# MySens-easyESP32-V02b-001.net
KiCad netlist of a schematic drawn in EAGLE
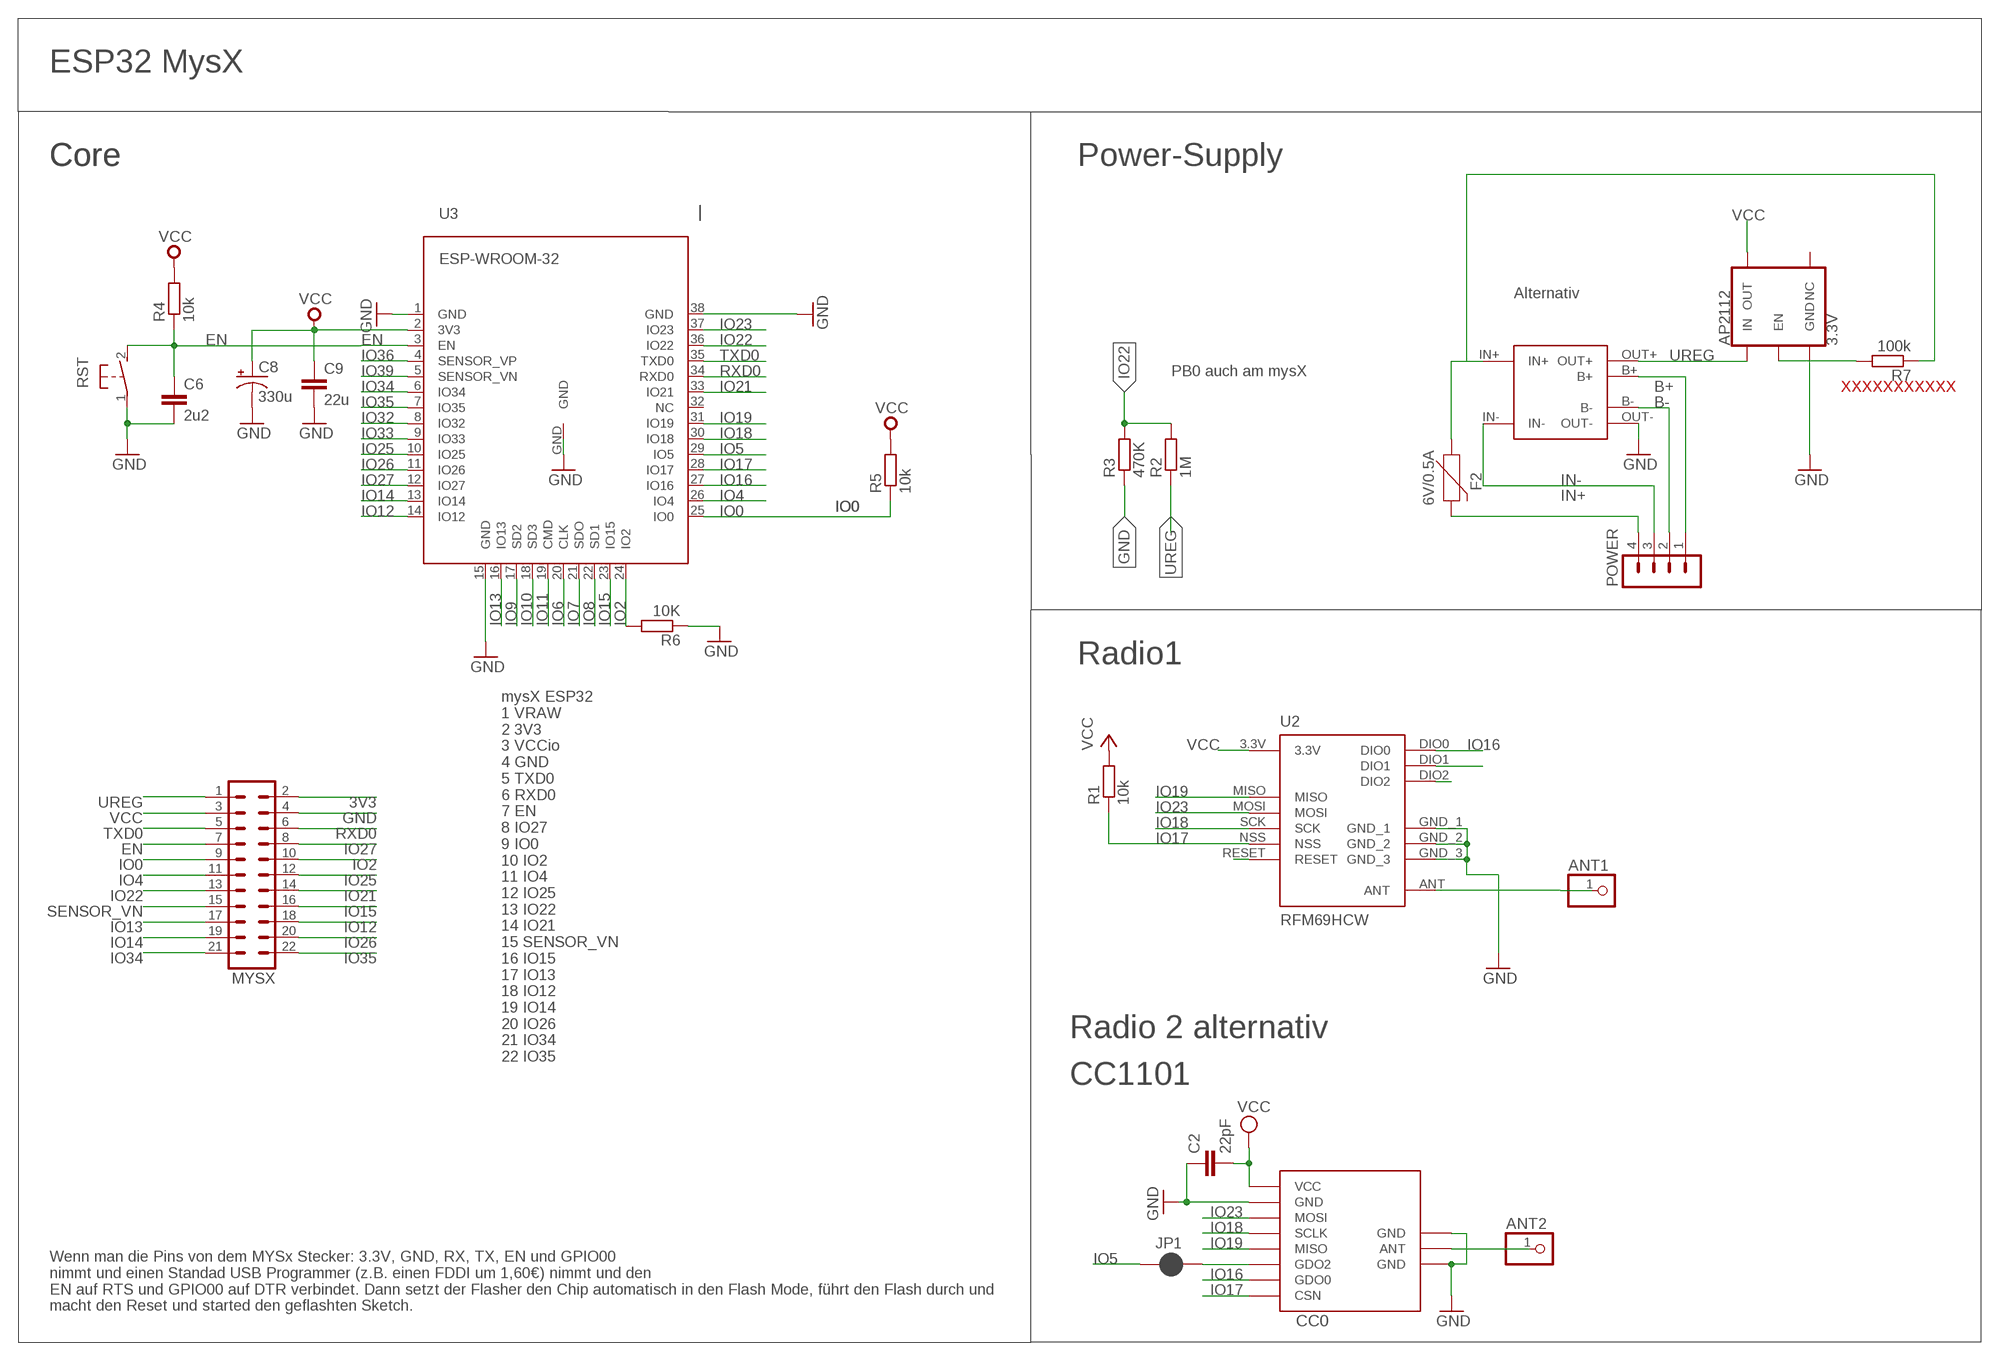
[diagram p0: schematic, sheet 1]

(export (version "E")
  (design (tool "Eeschema 10.0.6"))
  (components
    (comp (ref "ANT1")
      (value "PINHD-1X1")
      (footprint "eagle-import:1X01")
      (libsource (lib "eagle-import") (part "PINHD-1X1"))
    )
    (comp (ref "ANT2")
      (value "PINHD-1X1")
      (footprint "eagle-import:1X01")
      (libsource (lib "eagle-import") (part "PINHD-1X1"))
    )
    (comp (ref "AP2112")
      (value "3.3V")
      (footprint "eagle-import:SOT23-5")
      (libsource (lib "eagle-import") (part "V_REG_AP2112K-3.3V"))
    )
    (comp (ref "C2")
      (value "22pF")
      (footprint "eagle-import:C0805")
      (libsource (lib "eagle-import") (part "C-EUC0805"))
    )
    (comp (ref "C6")
      (value "2u2")
      (footprint "eagle-import:C0805")
      (libsource (lib "eagle-import") (part "rcl@1_C-EUC0805"))
    )
    (comp (ref "C8")
      (value "330u")
      (footprint "eagle-import:VISHAY_C")
      (libsource (lib "eagle-import") (part "CAP_POLSMD"))
    )
    (comp (ref "C9")
      (value "22u")
      (footprint "eagle-import:C0805")
      (libsource (lib "eagle-import") (part "rcl@1_C-EUC0805"))
    )
    (comp (ref "CC0")
      (value "CC1101")
      (footprint "eagle-import:CC1101_MODULE1_SMD")
      (libsource (lib "eagle-import") (part "CC1101_MODULE1SMD"))
    )
    (comp (ref "F2")
      (value "6V/0.5A")
      (footprint "eagle-import:1206")
      (libsource (lib "eagle-import") (part "PPTC_HALF-AMP"))
    )
    (comp (ref "JP1")
      (value "JUMPER-SMT_2_NC_PASTE_NO-SILK")
      (footprint "eagle-import:SMT-JUMPER_2_NC_PASTE_NO-SILK")
      (libsource (lib "eagle-import") (part "JUMPER-SMT_2_NC_PASTE_NO-SILK"))
    )
    (comp (ref "MYSX")
      (value "MA11-2")
      (footprint "eagle-import:MA11-2")
      (libsource (lib "eagle-import") (part "MA11-2"))
    )
    (comp (ref "POWER")
      (value "MA04-1")
      (footprint "eagle-import:MA04-1")
      (libsource (lib "eagle-import") (part "MA04-1"))
    )
    (comp (ref "R1")
      (value "10k")
      (footprint "eagle-import:M0805")
      (libsource (lib "eagle-import") (part "R-EU_M0805"))
    )
    (comp (ref "R2")
      (value "1M")
      (footprint "eagle-import:M0805")
      (libsource (lib "eagle-import") (part "R-EU_M0805"))
    )
    (comp (ref "R3")
      (value "470K")
      (footprint "eagle-import:M0805")
      (libsource (lib "eagle-import") (part "R-EU_M0805"))
    )
    (comp (ref "R4")
      (value "10k")
      (footprint "eagle-import:M0805")
      (libsource (lib "eagle-import") (part "rcl@1_R-EU_M0805"))
    )
    (comp (ref "R5")
      (value "10k")
      (footprint "eagle-import:R0603")
      (libsource (lib "eagle-import") (part "R-EU_R0603"))
    )
    (comp (ref "R6")
      (value "10K")
      (footprint "eagle-import:M0805")
      (libsource (lib "eagle-import") (part "R-EU_M0805"))
    )
    (comp (ref "R7")
      (value "100k")
      (footprint "eagle-import:M0805")
      (libsource (lib "eagle-import") (part "R-EU_M0805"))
    )
    (comp (ref "RST")
      (value "DTSM-3")
      (footprint "eagle-import:DTSM-3")
      (libsource (lib "eagle-import") (part "DTSM-3"))
    )
    (comp (ref "TP4056")
      (value "TP4056-MODULE")
      (footprint "eagle-import:TP4056-LITHIUM-PROTECTED-MODULE")
      (libsource (lib "eagle-import") (part "TP4056-MODULE"))
    )
    (comp (ref "U2")
      (value "RFM69HCW")
      (footprint "eagle-import:RFM69HCW-XXXS2")
      (libsource (lib "eagle-import") (part "RFM69HCW"))
    )
    (comp (ref "U3")
      (value "ESP-WROOM-32")
      (footprint "eagle-import:ESP-WROOM-32")
      (libsource (lib "eagle-import") (part "ESP-WROOM-32"))
    )
  )
  (nets
    (net (code "1") (name "/3V3") (class "Default")
      (node (ref "MYSX") (pin "2") (pinfunction "2_2") (pintype "passive"))
    )
    (net (code "2") (name "/B+") (class "Default")
      (node (ref "POWER") (pin "1") (pinfunction "1_1") (pintype "passive"))
      (node (ref "TP4056") (pin "B+") (pinfunction "B+_B+") (pintype "power_in"))
    )
    (net (code "3") (name "/B-") (class "Default")
      (node (ref "POWER") (pin "2") (pinfunction "2_2") (pintype "passive"))
      (node (ref "TP4056") (pin "B-") (pinfunction "B-_B-") (pintype "power_in"))
    )
    (net (code "4") (name "/EN") (class "Default")
      (node (ref "C6") (pin "1") (pinfunction "1_1") (pintype "passive"))
      (node (ref "MYSX") (pin "7") (pinfunction "7_7") (pintype "passive"))
      (node (ref "R4") (pin "1") (pinfunction "1_1") (pintype "passive"))
      (node (ref "RST") (pin "2") (pinfunction "2_2") (pintype "passive"))
      (node (ref "U3") (pin "3") (pinfunction "EN_3") (pintype "bidirectional"))
    )
    (net (code "5") (name "/IN+") (class "Default")
      (node (ref "F2") (pin "2") (pinfunction "2_2") (pintype "bidirectional"))
      (node (ref "POWER") (pin "4") (pinfunction "4_4") (pintype "passive"))
    )
    (net (code "6") (name "/IN-") (class "Default")
      (node (ref "POWER") (pin "3") (pinfunction "3_3") (pintype "passive"))
      (node (ref "TP4056") (pin "IN-") (pinfunction "IN-_IN-") (pintype "power_in"))
    )
    (net (code "7") (name "/IO0") (class "Default")
      (node (ref "MYSX") (pin "9") (pinfunction "9_9") (pintype "passive"))
      (node (ref "R5") (pin "1") (pinfunction "1_1") (pintype "passive"))
      (node (ref "U3") (pin "25") (pinfunction "IO0_25") (pintype "bidirectional"))
    )
    (net (code "8") (name "/IO2") (class "Default")
      (node (ref "MYSX") (pin "10") (pinfunction "10_10") (pintype "passive"))
      (node (ref "R6") (pin "2") (pinfunction "2_2") (pintype "passive"))
      (node (ref "U3") (pin "24") (pinfunction "IO2_24") (pintype "bidirectional"))
    )
    (net (code "9") (name "/IO4") (class "Default")
      (node (ref "MYSX") (pin "11") (pinfunction "11_11") (pintype "passive"))
      (node (ref "U3") (pin "26") (pinfunction "IO4_26") (pintype "bidirectional"))
    )
    (net (code "10") (name "/IO5") (class "Default")
      (node (ref "JP1") (pin "1") (pinfunction "1_1") (pintype "passive"))
      (node (ref "U3") (pin "29") (pinfunction "IO5_29") (pintype "bidirectional"))
    )
    (net (code "11") (name "/IO6") (class "Default")
      (node (ref "U3") (pin "20") (pinfunction "CLK_20") (pintype "bidirectional"))
    )
    (net (code "12") (name "/IO7") (class "Default")
      (node (ref "U3") (pin "21") (pinfunction "SDO_21") (pintype "bidirectional"))
    )
    (net (code "13") (name "/IO8") (class "Default")
      (node (ref "U3") (pin "22") (pinfunction "SD1_22") (pintype "bidirectional"))
    )
    (net (code "14") (name "/IO9") (class "Default")
      (node (ref "U3") (pin "17") (pinfunction "SD2_17") (pintype "bidirectional"))
    )
    (net (code "15") (name "/IO10") (class "Default")
      (node (ref "U3") (pin "18") (pinfunction "SD3_18") (pintype "bidirectional"))
    )
    (net (code "16") (name "/IO11") (class "Default")
      (node (ref "U3") (pin "19") (pinfunction "CMD_19") (pintype "bidirectional"))
    )
    (net (code "17") (name "/IO12") (class "Default")
      (node (ref "MYSX") (pin "18") (pinfunction "18_18") (pintype "passive"))
      (node (ref "U3") (pin "14") (pinfunction "IO12_14") (pintype "bidirectional"))
    )
    (net (code "18") (name "/IO13") (class "Default")
      (node (ref "MYSX") (pin "17") (pinfunction "17_17") (pintype "passive"))
      (node (ref "U3") (pin "16") (pinfunction "IO13_16") (pintype "bidirectional"))
    )
    (net (code "19") (name "/IO14") (class "Default")
      (node (ref "MYSX") (pin "19") (pinfunction "19_19") (pintype "passive"))
      (node (ref "U3") (pin "13") (pinfunction "IO14_13") (pintype "bidirectional"))
    )
    (net (code "20") (name "/IO15") (class "Default")
      (node (ref "MYSX") (pin "16") (pinfunction "16_16") (pintype "passive"))
      (node (ref "U3") (pin "23") (pinfunction "IO15_23") (pintype "bidirectional"))
    )
    (net (code "21") (name "/IO16") (class "Default")
      (node (ref "CC0") (pin "GDO0") (pinfunction "GDO0_GDO0") (pintype "bidirectional"))
      (node (ref "U2") (pin "DIO0") (pinfunction "DIO0_DIO0") (pintype "bidirectional"))
      (node (ref "U3") (pin "27") (pinfunction "IO16_27") (pintype "bidirectional"))
    )
    (net (code "22") (name "/IO17") (class "Default")
      (node (ref "CC0") (pin "CSN") (pinfunction "CSN_CSN") (pintype "bidirectional"))
      (node (ref "R1") (pin "1") (pinfunction "1_1") (pintype "passive"))
      (node (ref "U2") (pin "NSS") (pinfunction "NSS_NSS") (pintype "input"))
      (node (ref "U3") (pin "28") (pinfunction "IO17_28") (pintype "bidirectional"))
    )
    (net (code "23") (name "/IO18") (class "Default")
      (node (ref "CC0") (pin "SCLK") (pinfunction "SCLK_SCLK") (pintype "bidirectional"))
      (node (ref "U2") (pin "SCK") (pinfunction "SCK_SCK") (pintype "input"))
      (node (ref "U3") (pin "30") (pinfunction "IO18_30") (pintype "bidirectional"))
    )
    (net (code "24") (name "/IO19") (class "Default")
      (node (ref "CC0") (pin "MISO") (pinfunction "MISO_MISO") (pintype "bidirectional"))
      (node (ref "U2") (pin "MISO") (pinfunction "MISO_MISO") (pintype "bidirectional"))
      (node (ref "U3") (pin "31") (pinfunction "IO19_31") (pintype "bidirectional"))
    )
    (net (code "25") (name "/IO21") (class "Default")
      (node (ref "MYSX") (pin "14") (pinfunction "14_14") (pintype "passive"))
      (node (ref "U3") (pin "33") (pinfunction "IO21_33") (pintype "bidirectional"))
    )
    (net (code "26") (name "/IO23") (class "Default")
      (node (ref "CC0") (pin "MOSI") (pinfunction "MOSI_MOSI") (pintype "bidirectional"))
      (node (ref "U2") (pin "MOSI") (pinfunction "MOSI_MOSI") (pintype "input"))
      (node (ref "U3") (pin "37") (pinfunction "IO23_37") (pintype "bidirectional"))
    )
    (net (code "27") (name "/IO25") (class "Default")
      (node (ref "MYSX") (pin "12") (pinfunction "12_12") (pintype "passive"))
      (node (ref "U3") (pin "10") (pinfunction "IO25_10") (pintype "bidirectional"))
    )
    (net (code "28") (name "/IO26") (class "Default")
      (node (ref "MYSX") (pin "20") (pinfunction "20_20") (pintype "passive"))
      (node (ref "U3") (pin "11") (pinfunction "IO26_11") (pintype "bidirectional"))
    )
    (net (code "29") (name "/IO27") (class "Default")
      (node (ref "MYSX") (pin "8") (pinfunction "8_8") (pintype "passive"))
      (node (ref "U3") (pin "12") (pinfunction "IO27_12") (pintype "bidirectional"))
    )
    (net (code "30") (name "/IO32") (class "Default")
      (node (ref "U3") (pin "8") (pinfunction "IO32_8") (pintype "bidirectional"))
    )
    (net (code "31") (name "/IO33") (class "Default")
      (node (ref "U3") (pin "9") (pinfunction "IO33_9") (pintype "bidirectional"))
    )
    (net (code "32") (name "/IO34") (class "Default")
      (node (ref "MYSX") (pin "21") (pinfunction "21_21") (pintype "passive"))
      (node (ref "U3") (pin "6") (pinfunction "IO34_6") (pintype "bidirectional"))
    )
    (net (code "33") (name "/IO35") (class "Default")
      (node (ref "MYSX") (pin "22") (pinfunction "22_22") (pintype "passive"))
      (node (ref "U3") (pin "7") (pinfunction "IO35_7") (pintype "bidirectional"))
    )
    (net (code "34") (name "/IO36") (class "Default")
      (node (ref "U3") (pin "4") (pinfunction "SENSOR_VP_4") (pintype "bidirectional"))
    )
    (net (code "35") (name "/IO39") (class "Default")
      (node (ref "U3") (pin "5") (pinfunction "SENSOR_VN_5") (pintype "bidirectional"))
    )
    (net (code "36") (name "/RXD0") (class "Default")
      (node (ref "MYSX") (pin "6") (pinfunction "6_6") (pintype "passive"))
      (node (ref "U3") (pin "34") (pinfunction "RXD0_34") (pintype "bidirectional"))
    )
    (net (code "37") (name "/SENSOR_VN") (class "Default")
      (node (ref "MYSX") (pin "15") (pinfunction "15_15") (pintype "passive"))
    )
    (net (code "38") (name "/TXD0") (class "Default")
      (node (ref "MYSX") (pin "5") (pinfunction "5_5") (pintype "passive"))
      (node (ref "U3") (pin "35") (pinfunction "TXD0_35") (pintype "bidirectional"))
    )
    (net (code "39") (name "GND") (class "Default")
      (node (ref "AP2112") (pin "2") (pinfunction "GND_2") (pintype "input"))
      (node (ref "C2") (pin "1") (pinfunction "1_1") (pintype "passive"))
      (node (ref "C6") (pin "2") (pinfunction "2_2") (pintype "passive"))
      (node (ref "C8") (pin "-") (pinfunction "-_-") (pintype "passive"))
      (node (ref "C9") (pin "2") (pinfunction "2_2") (pintype "passive"))
      (node (ref "CC0") (pin "GND@0") (pinfunction "GND_GND@0") (pintype "power_in"))
      (node (ref "CC0") (pin "GND@1") (pinfunction "GND_GND@1") (pintype "power_in"))
      (node (ref "CC0") (pin "GND@2") (pinfunction "GND_GND@2") (pintype "power_in"))
      (node (ref "MYSX") (pin "4") (pinfunction "4_4") (pintype "passive"))
      (node (ref "R3") (pin "1") (pinfunction "1_1") (pintype "passive"))
      (node (ref "R6") (pin "1") (pinfunction "1_1") (pintype "passive"))
      (node (ref "RST") (pin "1") (pinfunction "1_1") (pintype "passive"))
      (node (ref "TP4056") (pin "OUT-") (pinfunction "OUT-_OUT-") (pintype "power_in"))
      (node (ref "U2") (pin "GND_1") (pinfunction "GND_1_GND_1") (pintype "power_in"))
      (node (ref "U2") (pin "GND_2") (pinfunction "GND_2_GND_2") (pintype "power_in"))
      (node (ref "U2") (pin "GND_3") (pinfunction "GND_3_GND_3") (pintype "power_in"))
      (node (ref "U3") (pin "1") (pinfunction "GND_1") (pintype "bidirectional"))
      (node (ref "U3") (pin "15") (pinfunction "GND_15") (pintype "bidirectional"))
      (node (ref "U3") (pin "38") (pinfunction "GND_38") (pintype "bidirectional"))
      (node (ref "U3") (pin "GND") (pinfunction "GND_GND") (pintype "bidirectional"))
    )
    (net (code "40") (name "IO22") (class "Default")
      (node (ref "MYSX") (pin "13") (pinfunction "13_13") (pintype "passive"))
      (node (ref "R2") (pin "2") (pinfunction "2_2") (pintype "passive"))
      (node (ref "R3") (pin "2") (pinfunction "2_2") (pintype "passive"))
      (node (ref "U3") (pin "36") (pinfunction "IO22_36") (pintype "bidirectional"))
    )
    (net (code "41") (name "Net-(ANT1-Pad1)") (class "Default")
      (node (ref "ANT1") (pin "1") (pinfunction "1_1") (pintype "passive"))
      (node (ref "U2") (pin "ANT") (pinfunction "ANT_ANT") (pintype "passive"))
    )
    (net (code "42") (name "Net-(ANT2-Pad1)") (class "Default")
      (node (ref "ANT2") (pin "1") (pinfunction "1_1") (pintype "passive"))
      (node (ref "CC0") (pin "ANT") (pinfunction "ANT_ANT") (pintype "output"))
    )
    (net (code "43") (name "Net-(AP2112-EN)") (class "Default")
      (node (ref "AP2112") (pin "3") (pinfunction "EN_3") (pintype "input"))
      (node (ref "R7") (pin "2") (pinfunction "2_2") (pintype "passive"))
    )
    (net (code "44") (name "Net-(CC0-PadGDO2)") (class "Default")
      (node (ref "CC0") (pin "GDO2") (pinfunction "GDO2_GDO2") (pintype "bidirectional"))
      (node (ref "JP1") (pin "2") (pinfunction "2_2") (pintype "passive"))
    )
    (net (code "45") (name "Net-(F2-Pad1)") (class "Default")
      (node (ref "F2") (pin "1") (pinfunction "1_1") (pintype "bidirectional"))
      (node (ref "R7") (pin "1") (pinfunction "1_1") (pintype "passive"))
      (node (ref "TP4056") (pin "IN+") (pinfunction "IN+_IN+") (pintype "power_in"))
    )
    (net (code "46") (name "UREG") (class "Default")
      (node (ref "AP2112") (pin "1") (pinfunction "IN_1") (pintype "input"))
      (node (ref "MYSX") (pin "1") (pinfunction "1_1") (pintype "passive"))
      (node (ref "R2") (pin "1") (pinfunction "1_1") (pintype "passive"))
      (node (ref "TP4056") (pin "OUT+") (pinfunction "OUT+_OUT+") (pintype "power_in"))
    )
    (net (code "47") (name "VCC") (class "Default")
      (node (ref "AP2112") (pin "5") (pinfunction "OUT_5") (pintype "passive"))
      (node (ref "C2") (pin "2") (pinfunction "2_2") (pintype "passive"))
      (node (ref "C8") (pin "+") (pinfunction "+_+") (pintype "passive"))
      (node (ref "C9") (pin "1") (pinfunction "1_1") (pintype "passive"))
      (node (ref "CC0") (pin "VCC") (pinfunction "VCC_VCC") (pintype "power_in"))
      (node (ref "MYSX") (pin "3") (pinfunction "3_3") (pintype "passive"))
      (node (ref "R1") (pin "2") (pinfunction "2_2") (pintype "passive"))
      (node (ref "R4") (pin "2") (pinfunction "2_2") (pintype "passive"))
      (node (ref "R5") (pin "2") (pinfunction "2_2") (pintype "passive"))
      (node (ref "U2") (pin "3.3V") (pinfunction "3.3V_3.3V") (pintype "power_in"))
      (node (ref "U3") (pin "2") (pinfunction "3V3_2") (pintype "bidirectional"))
    )
    (net (code "48") (name "unconnected-(AP2112-NC-Pad4)") (class "Default")
      (node (ref "AP2112") (pin "4") (pinfunction "NC_4") (pintype "no_connect"))
    )
    (net (code "49") (name "unconnected-(U2-PadDIO1)") (class "Default")
      (node (ref "U2") (pin "DIO1") (pinfunction "DIO1_DIO1") (pintype "bidirectional"))
    )
    (net (code "50") (name "unconnected-(U2-PadDIO2)") (class "Default")
      (node (ref "U2") (pin "DIO2") (pinfunction "DIO2_DIO2") (pintype "bidirectional"))
    )
    (net (code "51") (name "unconnected-(U2-PadRESET)") (class "Default")
      (node (ref "U2") (pin "RESET") (pinfunction "RESET_RESET") (pintype "input"))
    )
    (net (code "52") (name "unconnected-(U3-NC-Pad32)") (class "Default")
      (node (ref "U3") (pin "32") (pinfunction "NC_32") (pintype "bidirectional"))
    )
  )
)
